# c116-vclfo.net
KiCad netlist of a schematic drawn in EAGLE
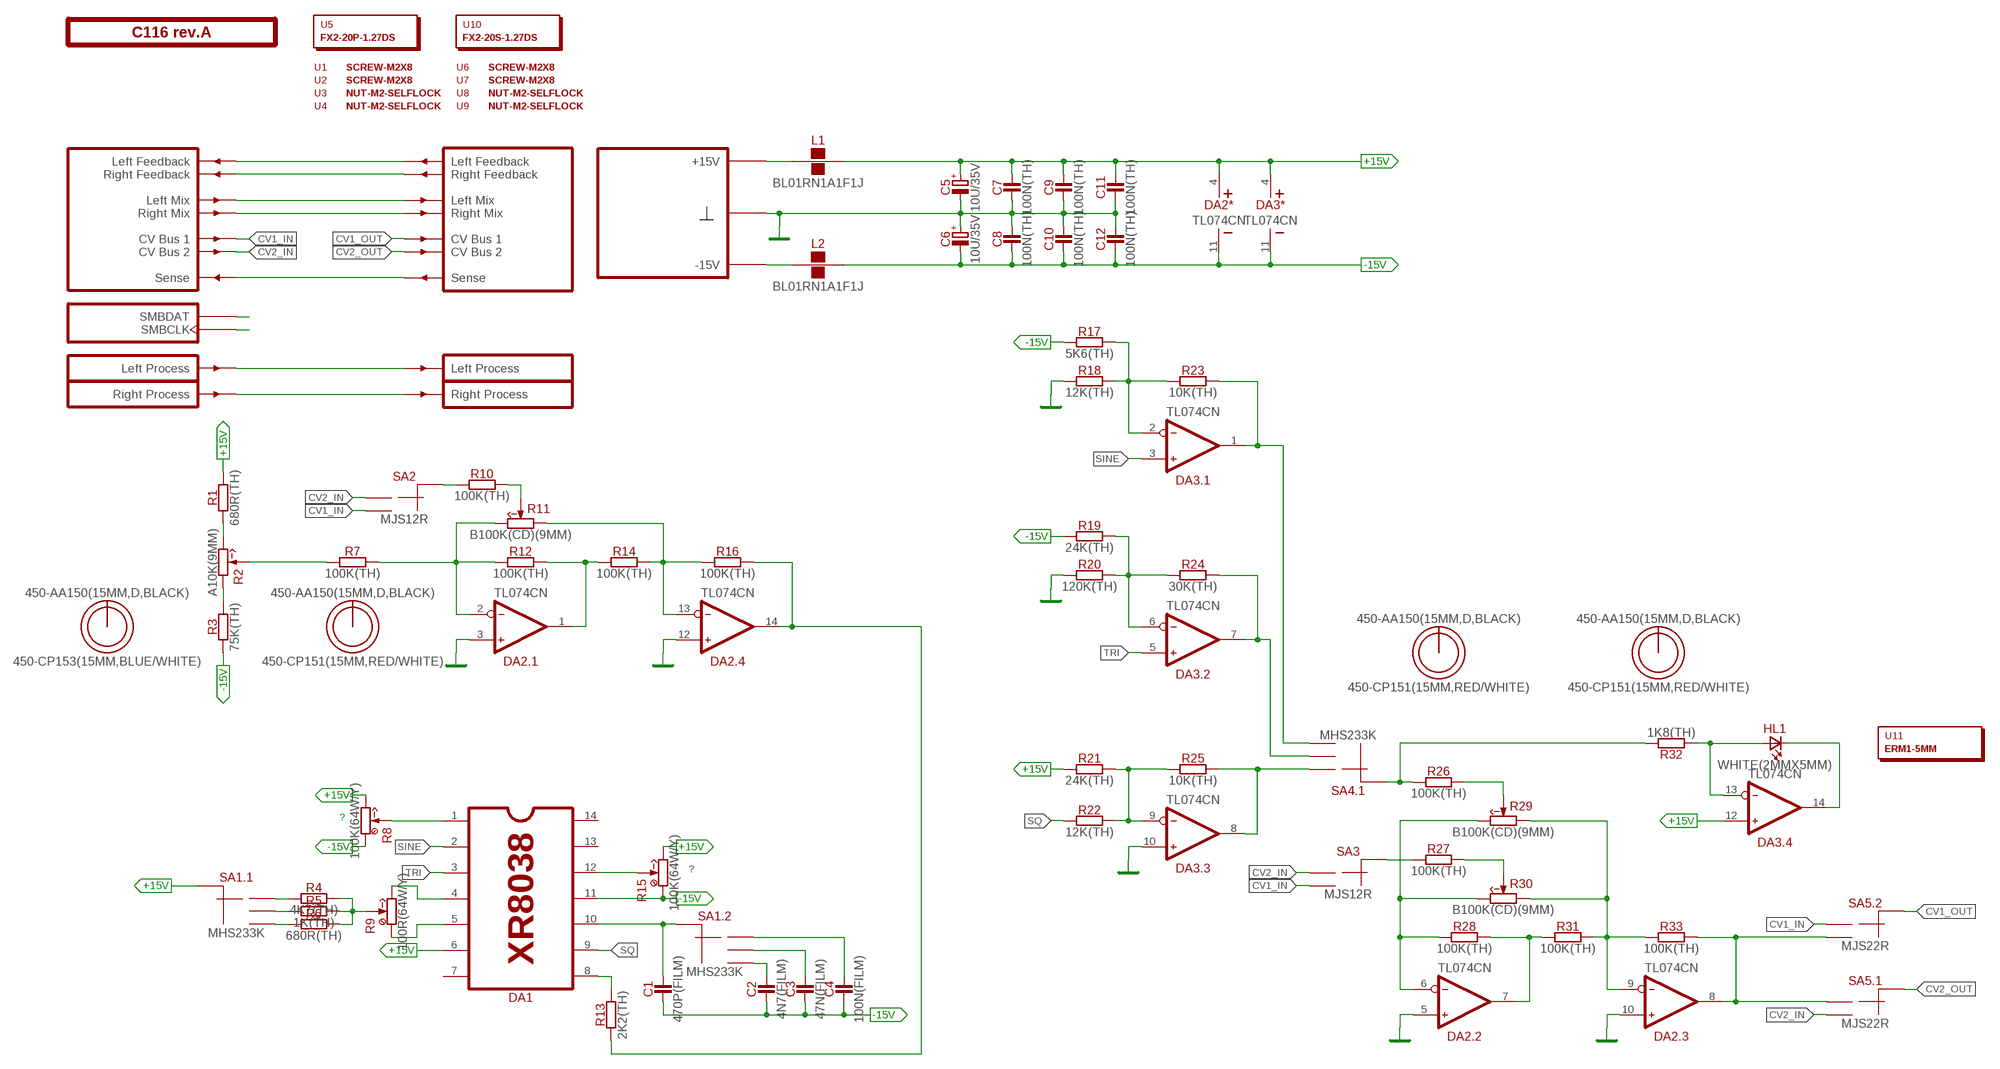
[diagram p0: schematic, sheet 1]

(export (version "E")
  (design (tool "Eeschema 10.0.6"))
  (components
    (comp (ref "C1")
      (value "470P(FILM)")
      (footprint "eagle-import:C050-055X075")
      (libsource (lib "eagle-import") (part "?470P(FILM)"))
    )
    (comp (ref "C2")
      (value "4N7(FILM)")
      (footprint "eagle-import:C050-025X075")
      (libsource (lib "eagle-import") (part "?4N7(FILM)"))
    )
    (comp (ref "C3")
      (value "47N(FILM)")
      (footprint "eagle-import:C050-025X075")
      (libsource (lib "eagle-import") (part "?47N(FILM)"))
    )
    (comp (ref "C4")
      (value "100N(FILM)")
      (footprint "eagle-import:C050-025X075")
      (libsource (lib "eagle-import") (part "?100N(FILM)"))
    )
    (comp (ref "C5")
      (value "10U/35V")
      (footprint "eagle-import:E2-5")
      (libsource (lib "eagle-import") (part "?10U/35V"))
    )
    (comp (ref "C6")
      (value "10U/35V")
      (footprint "eagle-import:E2-5")
      (libsource (lib "eagle-import") (part "?10U/35V"))
    )
    (comp (ref "C7")
      (value "100N(TH)")
      (footprint "eagle-import:C050-024X044")
      (libsource (lib "eagle-import") (part "?100N(TH)"))
    )
    (comp (ref "C8")
      (value "100N(TH)")
      (footprint "eagle-import:C050-024X044")
      (libsource (lib "eagle-import") (part "?100N(TH)"))
    )
    (comp (ref "C9")
      (value "100N(TH)")
      (footprint "eagle-import:C050-024X044")
      (libsource (lib "eagle-import") (part "?100N(TH)"))
    )
    (comp (ref "C10")
      (value "100N(TH)")
      (footprint "eagle-import:C050-024X044")
      (libsource (lib "eagle-import") (part "?100N(TH)"))
    )
    (comp (ref "C11")
      (value "100N(TH)")
      (footprint "eagle-import:C050-024X044")
      (libsource (lib "eagle-import") (part "?100N(TH)"))
    )
    (comp (ref "C12")
      (value "100N(TH)")
      (footprint "eagle-import:C050-024X044")
      (libsource (lib "eagle-import") (part "?100N(TH)"))
    )
    (comp (ref "DA1")
      (value "XR8038")
      (footprint "eagle-import:DIP-14")
      (libsource (lib "eagle-import") (part "XR8038"))
    )
    (comp (ref "DA2")
      (value "TL074CN")
      (footprint "eagle-import:DIP-14")
      (libsource (lib "eagle-import") (part "TL074CN"))
    )
    (comp (ref "DA3")
      (value "TL074CN")
      (footprint "eagle-import:DIP-14")
      (libsource (lib "eagle-import") (part "TL074CN"))
    )
    (comp (ref "HL1")
      (value "WHITE(2MMX5MM)")
      (footprint "eagle-import:LED2X5")
      (libsource (lib "eagle-import") (part "?(2MMX5MM)WHITE"))
    )
    (comp (ref "L1")
      (value "BL01RN1A1F1J")
      (footprint "eagle-import:BL01RN1A")
      (libsource (lib "eagle-import") (part "BL01RN1A?1F1J"))
    )
    (comp (ref "L2")
      (value "BL01RN1A1F1J")
      (footprint "eagle-import:BL01RN1A")
      (libsource (lib "eagle-import") (part "BL01RN1A?1F1J"))
    )
    (comp (ref "O1")
      (value "450-AA150(15MM,D,BLACK)")
      (footprint "eagle-import:EMPTY")
      (libsource (lib "eagle-import") (part "450-AA?150(15MM,D,BLACK)"))
    )
    (comp (ref "O2")
      (value "450-CP153(15MM,BLUE/WHITE)")
      (footprint "eagle-import:EMPTY")
      (libsource (lib "eagle-import") (part "450-C?P153(15MM,BLUE/WHITE)"))
    )
    (comp (ref "O3")
      (value "450-AA150(15MM,D,BLACK)")
      (footprint "eagle-import:EMPTY")
      (libsource (lib "eagle-import") (part "450-AA?150(15MM,D,BLACK)"))
    )
    (comp (ref "O4")
      (value "450-CP151(15MM,RED/WHITE)")
      (footprint "eagle-import:EMPTY")
      (libsource (lib "eagle-import") (part "450-C?P151(15MM,RED/WHITE)"))
    )
    (comp (ref "O5")
      (value "450-AA150(15MM,D,BLACK)")
      (footprint "eagle-import:EMPTY")
      (libsource (lib "eagle-import") (part "450-AA?150(15MM,D,BLACK)"))
    )
    (comp (ref "O6")
      (value "450-CP151(15MM,RED/WHITE)")
      (footprint "eagle-import:EMPTY")
      (libsource (lib "eagle-import") (part "450-C?P151(15MM,RED/WHITE)"))
    )
    (comp (ref "O7")
      (value "450-AA150(15MM,D,BLACK)")
      (footprint "eagle-import:EMPTY")
      (libsource (lib "eagle-import") (part "450-AA?150(15MM,D,BLACK)"))
    )
    (comp (ref "O8")
      (value "450-CP151(15MM,RED/WHITE)")
      (footprint "eagle-import:EMPTY")
      (libsource (lib "eagle-import") (part "450-C?P151(15MM,RED/WHITE)"))
    )
    (comp (ref "PCB1")
      (value "C116 rev.A")
      (footprint "eagle-import:ST2-BOARD-74")
      (libsource (lib "eagle-import") (part "ST2-BOARD-?74"))
    )
    (comp (ref "R1")
      (value "680R(TH)")
      (footprint "eagle-import:R-0207_10")
      (libsource (lib "eagle-import") (part "?680R(TH)"))
    )
    (comp (ref "R2")
      (value "A10K(9MM)")
      (footprint "eagle-import:RV09-SINGLE")
      (libsource (lib "eagle-import") (part "?A10K(9MM)"))
    )
    (comp (ref "R3")
      (value "75K(TH)")
      (footprint "eagle-import:R-0207_10")
      (libsource (lib "eagle-import") (part "?75K(TH)"))
    )
    (comp (ref "R4")
      (value "4K7(TH)")
      (footprint "eagle-import:R-0207_10")
      (libsource (lib "eagle-import") (part "?4K7(TH)"))
    )
    (comp (ref "R5")
      (value "1K(TH)")
      (footprint "eagle-import:R-0207_10")
      (libsource (lib "eagle-import") (part "?1K(TH)"))
    )
    (comp (ref "R6")
      (value "680R(TH)")
      (footprint "eagle-import:R-0207_10")
      (libsource (lib "eagle-import") (part "?680R(TH)"))
    )
    (comp (ref "R7")
      (value "100K(TH)")
      (footprint "eagle-import:R-0207_10")
      (libsource (lib "eagle-import") (part "?100K(TH)"))
    )
    (comp (ref "R8")
      (value "100K(64W/Y)")
      (footprint "eagle-import:64W")
      (libsource (lib "eagle-import") (part "?(64W/Y)100K"))
    )
    (comp (ref "R9")
      (value "100R(64W/Y)")
      (footprint "eagle-import:64W")
      (libsource (lib "eagle-import") (part "?(64W/Y)100R"))
    )
    (comp (ref "R10")
      (value "100K(TH)")
      (footprint "eagle-import:R-0207_10")
      (libsource (lib "eagle-import") (part "?100K(TH)"))
    )
    (comp (ref "R11")
      (value "B100K(CD)(9MM)")
      (footprint "eagle-import:RV09-SINGLE")
      (libsource (lib "eagle-import") (part "?B100K(CD)(9MM)"))
    )
    (comp (ref "R12")
      (value "100K(TH)")
      (footprint "eagle-import:R-0207_10")
      (libsource (lib "eagle-import") (part "?100K(TH)"))
    )
    (comp (ref "R13")
      (value "2K2(TH)")
      (footprint "eagle-import:R-0207_10")
      (libsource (lib "eagle-import") (part "?2K2(TH)"))
    )
    (comp (ref "R14")
      (value "100K(TH)")
      (footprint "eagle-import:R-0207_10")
      (libsource (lib "eagle-import") (part "?100K(TH)"))
    )
    (comp (ref "R15")
      (value "100K(64W/Y)")
      (footprint "eagle-import:64W")
      (libsource (lib "eagle-import") (part "?(64W/Y)100K"))
    )
    (comp (ref "R16")
      (value "100K(TH)")
      (footprint "eagle-import:R-0207_10")
      (libsource (lib "eagle-import") (part "?100K(TH)"))
    )
    (comp (ref "R17")
      (value "5K6(TH)")
      (footprint "eagle-import:R-0207_10")
      (libsource (lib "eagle-import") (part "?5K6(TH)"))
    )
    (comp (ref "R18")
      (value "12K(TH)")
      (footprint "eagle-import:R-0207_10")
      (libsource (lib "eagle-import") (part "?12K(TH)"))
    )
    (comp (ref "R19")
      (value "24K(TH)")
      (footprint "eagle-import:R-0207_10")
      (libsource (lib "eagle-import") (part "?24K(TH)"))
    )
    (comp (ref "R20")
      (value "120K(TH)")
      (footprint "eagle-import:R-0207_10")
      (libsource (lib "eagle-import") (part "?120K(TH)"))
    )
    (comp (ref "R21")
      (value "24K(TH)")
      (footprint "eagle-import:R-0207_10")
      (libsource (lib "eagle-import") (part "?24K(TH)"))
    )
    (comp (ref "R22")
      (value "12K(TH)")
      (footprint "eagle-import:R-0207_10")
      (libsource (lib "eagle-import") (part "?12K(TH)"))
    )
    (comp (ref "R23")
      (value "10K(TH)")
      (footprint "eagle-import:R-0207_10")
      (libsource (lib "eagle-import") (part "?10K(TH)"))
    )
    (comp (ref "R24")
      (value "30K(TH)")
      (footprint "eagle-import:R-0207_10")
      (libsource (lib "eagle-import") (part "?30K(TH)"))
    )
    (comp (ref "R25")
      (value "10K(TH)")
      (footprint "eagle-import:R-0207_10")
      (libsource (lib "eagle-import") (part "?10K(TH)"))
    )
    (comp (ref "R26")
      (value "100K(TH)")
      (footprint "eagle-import:R-0207_10")
      (libsource (lib "eagle-import") (part "?100K(TH)"))
    )
    (comp (ref "R27")
      (value "100K(TH)")
      (footprint "eagle-import:R-0207_10")
      (libsource (lib "eagle-import") (part "?100K(TH)"))
    )
    (comp (ref "R28")
      (value "100K(TH)")
      (footprint "eagle-import:R-0207_10")
      (libsource (lib "eagle-import") (part "?100K(TH)"))
    )
    (comp (ref "R29")
      (value "B100K(CD)(9MM)")
      (footprint "eagle-import:RV09-SINGLE")
      (libsource (lib "eagle-import") (part "?B100K(CD)(9MM)"))
    )
    (comp (ref "R30")
      (value "B100K(CD)(9MM)")
      (footprint "eagle-import:RV09-SINGLE")
      (libsource (lib "eagle-import") (part "?B100K(CD)(9MM)"))
    )
    (comp (ref "R31")
      (value "100K(TH)")
      (footprint "eagle-import:R-0207_10")
      (libsource (lib "eagle-import") (part "?100K(TH)"))
    )
    (comp (ref "R32")
      (value "1K8(TH)")
      (footprint "eagle-import:R-0207_10")
      (libsource (lib "eagle-import") (part "?1K8(TH)"))
    )
    (comp (ref "R33")
      (value "100K(TH)")
      (footprint "eagle-import:R-0207_10")
      (libsource (lib "eagle-import") (part "?100K(TH)"))
    )
    (comp (ref "SA1")
      (value "MHS233K")
      (footprint "eagle-import:APEM-MHS233K")
      (libsource (lib "eagle-import") (part "MHS233K"))
    )
    (comp (ref "SA2")
      (value "MJS12R")
      (footprint "eagle-import:APEM-MJS12R")
      (libsource (lib "eagle-import") (part "MJS12R"))
    )
    (comp (ref "SA3")
      (value "MJS12R")
      (footprint "eagle-import:APEM-MJS12R")
      (libsource (lib "eagle-import") (part "MJS12R"))
    )
    (comp (ref "SA4")
      (value "MHS233K")
      (footprint "eagle-import:APEM-MHS233K")
      (libsource (lib "eagle-import") (part "MHS233K"))
    )
    (comp (ref "SA5")
      (value "MJS22R")
      (footprint "eagle-import:APEM-MJS22R")
      (libsource (lib "eagle-import") (part "MJS22R"))
    )
    (comp (ref "U1")
      (value "SCREW-M2X8")
      (footprint "eagle-import:EMPTY")
      (libsource (lib "eagle-import") (part "?SCREW-M2X8"))
    )
    (comp (ref "U2")
      (value "SCREW-M2X8")
      (footprint "eagle-import:EMPTY")
      (libsource (lib "eagle-import") (part "?SCREW-M2X8"))
    )
    (comp (ref "U3")
      (value "NUT-M2-SELFLOCK")
      (footprint "eagle-import:EMPTY")
      (libsource (lib "eagle-import") (part "?NUT-M2-SELFLOCK"))
    )
    (comp (ref "U4")
      (value "NUT-M2-SELFLOCK")
      (footprint "eagle-import:EMPTY")
      (libsource (lib "eagle-import") (part "?NUT-M2-SELFLOCK"))
    )
    (comp (ref "U5")
      (value "FX2-20P-1.27DS")
      (footprint "eagle-import:EMPTY")
      (libsource (lib "eagle-import") (part "?FX2-20P-1.27DS"))
    )
    (comp (ref "U6")
      (value "SCREW-M2X8")
      (footprint "eagle-import:EMPTY")
      (libsource (lib "eagle-import") (part "?SCREW-M2X8"))
    )
    (comp (ref "U7")
      (value "SCREW-M2X8")
      (footprint "eagle-import:EMPTY")
      (libsource (lib "eagle-import") (part "?SCREW-M2X8"))
    )
    (comp (ref "U8")
      (value "NUT-M2-SELFLOCK")
      (footprint "eagle-import:EMPTY")
      (libsource (lib "eagle-import") (part "?NUT-M2-SELFLOCK"))
    )
    (comp (ref "U9")
      (value "NUT-M2-SELFLOCK")
      (footprint "eagle-import:EMPTY")
      (libsource (lib "eagle-import") (part "?NUT-M2-SELFLOCK"))
    )
    (comp (ref "U10")
      (value "FX2-20S-1.27DS")
      (footprint "eagle-import:EMPTY")
      (libsource (lib "eagle-import") (part "?FX2-20S-1.27DS"))
    )
    (comp (ref "U11")
      (value "ERM1-5MM")
      (footprint "eagle-import:EMPTY")
      (libsource (lib "eagle-import") (part "?ERM1-5MM"))
    )
  )
  (nets
    (net (code "1") (name "+15V") (class "Default")
      (node (ref "C11") (pin "2") (pinfunction "2_2") (pintype "passive"))
      (node (ref "C5") (pin "+") (pinfunction "+_+") (pintype "passive"))
      (node (ref "C7") (pin "2") (pinfunction "2_2") (pintype "passive"))
      (node (ref "C9") (pin "2") (pinfunction "2_2") (pintype "passive"))
      (node (ref "DA1") (pin "6") (pinfunction "6_6") (pintype "bidirectional"))
      (node (ref "DA2") (pin "4") (pinfunction "V+_4") (pintype "power_in"))
      (node (ref "DA3") (pin "12") (pinfunction "IN+_12") (pintype "input"))
      (node (ref "DA3") (pin "4") (pinfunction "V+_4") (pintype "power_in"))
      (node (ref "L1") (pin "2") (pinfunction "2_2") (pintype "passive"))
      (node (ref "R1") (pin "2") (pinfunction "2_2") (pintype "passive"))
      (node (ref "R15") (pin "3") (pinfunction "CW_3") (pintype "passive"))
      (node (ref "R21") (pin "1") (pinfunction "1_1") (pintype "passive"))
      (node (ref "R8") (pin "3") (pinfunction "CW_3") (pintype "passive"))
      (node (ref "SA1") (pin "CMN") (pinfunction "CM_CMN") (pintype "passive"))
    )
    (net (code "2") (name "-15V") (class "Default")
      (node (ref "C1") (pin "1") (pinfunction "1_1") (pintype "passive"))
      (node (ref "C10") (pin "1") (pinfunction "1_1") (pintype "passive"))
      (node (ref "C12") (pin "1") (pinfunction "1_1") (pintype "passive"))
      (node (ref "C2") (pin "1") (pinfunction "1_1") (pintype "passive"))
      (node (ref "C3") (pin "1") (pinfunction "1_1") (pintype "passive"))
      (node (ref "C4") (pin "1") (pinfunction "1_1") (pintype "passive"))
      (node (ref "C6") (pin "-") (pinfunction "-_-") (pintype "passive"))
      (node (ref "C8") (pin "1") (pinfunction "1_1") (pintype "passive"))
      (node (ref "DA1") (pin "11") (pinfunction "11_11") (pintype "bidirectional"))
      (node (ref "DA2") (pin "11") (pinfunction "V-_11") (pintype "power_in"))
      (node (ref "DA3") (pin "11") (pinfunction "V-_11") (pintype "power_in"))
      (node (ref "L2") (pin "2") (pinfunction "2_2") (pintype "passive"))
      (node (ref "R15") (pin "1") (pinfunction "CCW_1") (pintype "passive"))
      (node (ref "R17") (pin "1") (pinfunction "1_1") (pintype "passive"))
      (node (ref "R19") (pin "1") (pinfunction "1_1") (pintype "passive"))
      (node (ref "R3") (pin "1") (pinfunction "1_1") (pintype "passive"))
      (node (ref "R8") (pin "1") (pinfunction "CCW_1") (pintype "passive"))
    )
    (net (code "3") (name "CV1_IN") (class "Default")
      (node (ref "PCB1") (pin "ACV1") (pinfunction "CV1_ACV1") (pintype "bidirectional"))
      (node (ref "SA2") (pin "NO") (pinfunction "2_NO") (pintype "passive"))
      (node (ref "SA3") (pin "NO") (pinfunction "2_NO") (pintype "passive"))
      (node (ref "SA5") (pin "NC2") (pinfunction "1_NC2") (pintype "passive"))
    )
    (net (code "4") (name "CV1_OUT") (class "Default")
      (node (ref "PCB1") (pin "ACV1'") (pinfunction "CV1'_ACV1'") (pintype "bidirectional"))
      (node (ref "SA5") (pin "C2") (pinfunction "CM_C2") (pintype "passive"))
    )
    (net (code "5") (name "CV2_IN") (class "Default")
      (node (ref "PCB1") (pin "ACV2") (pinfunction "CV2_ACV2") (pintype "bidirectional"))
      (node (ref "SA2") (pin "NC") (pinfunction "1_NC") (pintype "passive"))
      (node (ref "SA3") (pin "NC") (pinfunction "1_NC") (pintype "passive"))
      (node (ref "SA5") (pin "NO1") (pinfunction "2_NO1") (pintype "passive"))
    )
    (net (code "6") (name "CV2_OUT") (class "Default")
      (node (ref "PCB1") (pin "ACV2'") (pinfunction "CV2'_ACV2'") (pintype "bidirectional"))
      (node (ref "SA5") (pin "C1") (pinfunction "CM_C1") (pintype "passive"))
    )
    (net (code "7") (name "GND") (class "Default")
      (node (ref "C10") (pin "2") (pinfunction "2_2") (pintype "passive"))
      (node (ref "C11") (pin "1") (pinfunction "1_1") (pintype "passive"))
      (node (ref "C12") (pin "2") (pinfunction "2_2") (pintype "passive"))
      (node (ref "C5") (pin "-") (pinfunction "-_-") (pintype "passive"))
      (node (ref "C6") (pin "+") (pinfunction "+_+") (pintype "passive"))
      (node (ref "C7") (pin "1") (pinfunction "1_1") (pintype "passive"))
      (node (ref "C8") (pin "2") (pinfunction "2_2") (pintype "passive"))
      (node (ref "C9") (pin "1") (pinfunction "1_1") (pintype "passive"))
      (node (ref "DA2") (pin "10") (pinfunction "IN+_10") (pintype "input"))
      (node (ref "DA2") (pin "12") (pinfunction "IN+_12") (pintype "input"))
      (node (ref "DA2") (pin "3") (pinfunction "IN+_3") (pintype "input"))
      (node (ref "DA2") (pin "5") (pinfunction "IN+_5") (pintype "input"))
      (node (ref "DA3") (pin "10") (pinfunction "IN+_10") (pintype "input"))
      (node (ref "PCB1") (pin "B4") (pinfunction "GND_B4") (pintype "bidirectional"))
      (node (ref "PCB1") (pin "B4'") (pinfunction "GND_B4'") (pintype "bidirectional"))
      (node (ref "PCB1") (pin "B5") (pinfunction "GND_B5") (pintype "bidirectional"))
      (node (ref "PCB1") (pin "B5'") (pinfunction "GND_B5'") (pintype "bidirectional"))
      (node (ref "PCB1") (pin "B6") (pinfunction "GND_B6") (pintype "bidirectional"))
      (node (ref "PCB1") (pin "B6'") (pinfunction "GND_B6'") (pintype "bidirectional"))
      (node (ref "PCB1") (pin "B7") (pinfunction "GND_B7") (pintype "bidirectional"))
      (node (ref "PCB1") (pin "B7'") (pinfunction "GND_B7'") (pintype "bidirectional"))
      (node (ref "PCB1") (pin "B8") (pinfunction "GND_B8") (pintype "bidirectional"))
      (node (ref "PCB1") (pin "B8'") (pinfunction "GND_B8'") (pintype "bidirectional"))
      (node (ref "R18") (pin "1") (pinfunction "1_1") (pintype "passive"))
      (node (ref "R20") (pin "1") (pinfunction "1_1") (pintype "passive"))
    )
    (net (code "8") (name "Net-(DA1-Pad1)") (class "Default")
      (node (ref "DA1") (pin "1") (pinfunction "1_1") (pintype "bidirectional"))
      (node (ref "R8") (pin "S") (pinfunction "W_S") (pintype "passive"))
      (node (ref "R8") (pin "S@1") (pinfunction "W_S@1") (pintype "passive"))
    )
    (net (code "9") (name "Net-(DA1-Pad8)") (class "Default")
      (node (ref "DA1") (pin "8") (pinfunction "8_8") (pintype "bidirectional"))
      (node (ref "R13") (pin "2") (pinfunction "2_2") (pintype "passive"))
    )
    (net (code "10") (name "Net-(DA1-Pad12)") (class "Default")
      (node (ref "DA1") (pin "12") (pinfunction "12_12") (pintype "bidirectional"))
      (node (ref "R15") (pin "S") (pinfunction "W_S") (pintype "passive"))
      (node (ref "R15") (pin "S@1") (pinfunction "W_S@1") (pintype "passive"))
    )
    (net (code "11") (name "Net-(DA2B-IN-)") (class "Default")
      (node (ref "DA2") (pin "2") (pinfunction "IN-_2") (pintype "input"))
      (node (ref "R11") (pin "3") (pinfunction "CW_3") (pintype "passive"))
      (node (ref "R12") (pin "1") (pinfunction "1_1") (pintype "passive"))
      (node (ref "R7") (pin "2") (pinfunction "2_2") (pintype "passive"))
    )
    (net (code "12") (name "Net-(DA2B-OUT)") (class "Default")
      (node (ref "DA2") (pin "1") (pinfunction "OUT_1") (pintype "output"))
      (node (ref "R12") (pin "2") (pinfunction "2_2") (pintype "passive"))
      (node (ref "R14") (pin "1") (pinfunction "1_1") (pintype "passive"))
    )
    (net (code "13") (name "Net-(DA2C-IN-)") (class "Default")
      (node (ref "DA2") (pin "6") (pinfunction "IN-_6") (pintype "input"))
      (node (ref "R28") (pin "1") (pinfunction "1_1") (pintype "passive"))
      (node (ref "R29") (pin "3") (pinfunction "CW_3") (pintype "passive"))
      (node (ref "R30") (pin "3") (pinfunction "CW_3") (pintype "passive"))
    )
    (net (code "14") (name "Net-(DA2C-OUT)") (class "Default")
      (node (ref "DA2") (pin "7") (pinfunction "OUT_7") (pintype "output"))
      (node (ref "R28") (pin "2") (pinfunction "2_2") (pintype "passive"))
      (node (ref "R31") (pin "1") (pinfunction "1_1") (pintype "passive"))
    )
    (net (code "15") (name "Net-(DA2D-IN-)") (class "Default")
      (node (ref "DA2") (pin "9") (pinfunction "IN-_9") (pintype "input"))
      (node (ref "R29") (pin "1") (pinfunction "CCW_1") (pintype "passive"))
      (node (ref "R30") (pin "1") (pinfunction "CCW_1") (pintype "passive"))
      (node (ref "R31") (pin "2") (pinfunction "2_2") (pintype "passive"))
      (node (ref "R33") (pin "1") (pinfunction "1_1") (pintype "passive"))
    )
    (net (code "16") (name "Net-(DA2D-OUT)") (class "Default")
      (node (ref "DA2") (pin "8") (pinfunction "OUT_8") (pintype "output"))
      (node (ref "R33") (pin "2") (pinfunction "2_2") (pintype "passive"))
      (node (ref "SA5") (pin "NC1") (pinfunction "1_NC1") (pintype "passive"))
      (node (ref "SA5") (pin "NO2") (pinfunction "2_NO2") (pintype "passive"))
    )
    (net (code "17") (name "Net-(DA2E-IN-)") (class "Default")
      (node (ref "DA2") (pin "13") (pinfunction "IN-_13") (pintype "input"))
      (node (ref "R11") (pin "1") (pinfunction "CCW_1") (pintype "passive"))
      (node (ref "R14") (pin "2") (pinfunction "2_2") (pintype "passive"))
      (node (ref "R16") (pin "1") (pinfunction "1_1") (pintype "passive"))
    )
    (net (code "18") (name "Net-(DA2E-OUT)") (class "Default")
      (node (ref "DA2") (pin "14") (pinfunction "OUT_14") (pintype "output"))
      (node (ref "R13") (pin "1") (pinfunction "1_1") (pintype "passive"))
      (node (ref "R16") (pin "2") (pinfunction "2_2") (pintype "passive"))
    )
    (net (code "19") (name "Net-(DA3B-IN-)") (class "Default")
      (node (ref "DA3") (pin "2") (pinfunction "IN-_2") (pintype "input"))
      (node (ref "R17") (pin "2") (pinfunction "2_2") (pintype "passive"))
      (node (ref "R18") (pin "2") (pinfunction "2_2") (pintype "passive"))
      (node (ref "R23") (pin "1") (pinfunction "1_1") (pintype "passive"))
    )
    (net (code "20") (name "Net-(DA3B-OUT)") (class "Default")
      (node (ref "DA3") (pin "1") (pinfunction "OUT_1") (pintype "output"))
      (node (ref "R23") (pin "2") (pinfunction "2_2") (pintype "passive"))
      (node (ref "SA4") (pin "3") (pinfunction "3_3") (pintype "passive"))
    )
    (net (code "21") (name "Net-(DA3C-IN-)") (class "Default")
      (node (ref "DA3") (pin "6") (pinfunction "IN-_6") (pintype "input"))
      (node (ref "R19") (pin "2") (pinfunction "2_2") (pintype "passive"))
      (node (ref "R20") (pin "2") (pinfunction "2_2") (pintype "passive"))
      (node (ref "R24") (pin "1") (pinfunction "1_1") (pintype "passive"))
    )
    (net (code "22") (name "Net-(DA3C-OUT)") (class "Default")
      (node (ref "DA3") (pin "7") (pinfunction "OUT_7") (pintype "output"))
      (node (ref "R24") (pin "2") (pinfunction "2_2") (pintype "passive"))
      (node (ref "SA4") (pin "2") (pinfunction "2_2") (pintype "passive"))
    )
    (net (code "23") (name "Net-(DA3D-IN-)") (class "Default")
      (node (ref "DA3") (pin "9") (pinfunction "IN-_9") (pintype "input"))
      (node (ref "R21") (pin "2") (pinfunction "2_2") (pintype "passive"))
      (node (ref "R22") (pin "2") (pinfunction "2_2") (pintype "passive"))
      (node (ref "R25") (pin "1") (pinfunction "1_1") (pintype "passive"))
    )
    (net (code "24") (name "Net-(DA3D-OUT)") (class "Default")
      (node (ref "DA3") (pin "8") (pinfunction "OUT_8") (pintype "output"))
      (node (ref "R25") (pin "2") (pinfunction "2_2") (pintype "passive"))
      (node (ref "SA4") (pin "1") (pinfunction "1_1") (pintype "passive"))
    )
    (net (code "25") (name "Net-(DA3E-IN-)") (class "Default")
      (node (ref "DA3") (pin "13") (pinfunction "IN-_13") (pintype "input"))
      (node (ref "HL1") (pin "A") (pinfunction "A_A") (pintype "passive"))
      (node (ref "R32") (pin "1") (pinfunction "1_1") (pintype "passive"))
    )
    (net (code "26") (name "Net-(DA3E-OUT)") (class "Default")
      (node (ref "DA3") (pin "14") (pinfunction "OUT_14") (pintype "output"))
      (node (ref "HL1") (pin "K") (pinfunction "C_K") (pintype "passive"))
    )
    (net (code "27") (name "Net-(L1-Pad1)") (class "Default")
      (node (ref "L1") (pin "1") (pinfunction "1_1") (pintype "passive"))
      (node (ref "PCB1") (pin "A+15") (pinfunction "P+15V_A+15") (pintype "bidirectional"))
      (node (ref "PCB1") (pin "A+15'") (pinfunction "P+15V_A+15'") (pintype "bidirectional"))
      (node (ref "PCB1") (pin "B+15") (pinfunction "P+15V_B+15") (pintype "bidirectional"))
      (node (ref "PCB1") (pin "B+15'") (pinfunction "P+15V_B+15'") (pintype "bidirectional"))
    )
    (net (code "28") (name "Net-(L2-Pad1)") (class "Default")
      (node (ref "L2") (pin "1") (pinfunction "1_1") (pintype "passive"))
      (node (ref "PCB1") (pin "A-15") (pinfunction "P-15V_A-15") (pintype "bidirectional"))
      (node (ref "PCB1") (pin "A-15'") (pinfunction "P-15V_A-15'") (pintype "bidirectional"))
      (node (ref "PCB1") (pin "B-15") (pinfunction "P-15V_B-15") (pintype "bidirectional"))
      (node (ref "PCB1") (pin "B-15'") (pinfunction "P-15V_B-15'") (pintype "bidirectional"))
    )
    (net (code "29") (name "Net-(PCB1B-INL)") (class "Default")
      (node (ref "PCB1") (pin "BINL") (pinfunction "INL_BINL") (pintype "bidirectional"))
      (node (ref "PCB1") (pin "BOUTL'") (pinfunction "OUTL_BOUTL'") (pintype "bidirectional"))
    )
    (net (code "30") (name "Net-(PCB1C-INR)") (class "Default")
      (node (ref "PCB1") (pin "BINR") (pinfunction "INR_BINR") (pintype "bidirectional"))
      (node (ref "PCB1") (pin "BOUTR'") (pinfunction "OUTR_BOUTR'") (pintype "bidirectional"))
    )
    (net (code "31") (name "Net-(PCB1F-LFBK)") (class "Default")
      (node (ref "PCB1") (pin "ALFBK") (pinfunction "LFBK_ALFBK") (pintype "bidirectional"))
      (node (ref "PCB1") (pin "ALFBK'") (pinfunction "LFBK'_ALFBK'") (pintype "bidirectional"))
    )
    (net (code "32") (name "Net-(PCB1F-LMIX)") (class "Default")
      (node (ref "PCB1") (pin "ALMIX") (pinfunction "LMIX_ALMIX") (pintype "bidirectional"))
      (node (ref "PCB1") (pin "ALMIX'") (pinfunction "LMIX'_ALMIX'") (pintype "bidirectional"))
    )
    (net (code "33") (name "Net-(PCB1F-RFBK)") (class "Default")
      (node (ref "PCB1") (pin "ARFBK") (pinfunction "RFBK_ARFBK") (pintype "bidirectional"))
      (node (ref "PCB1") (pin "ARFBK'") (pinfunction "RFBK'_ARFBK'") (pintype "bidirectional"))
    )
    (net (code "34") (name "Net-(PCB1F-RMIX)") (class "Default")
      (node (ref "PCB1") (pin "ARMIX") (pinfunction "RMIX_ARMIX") (pintype "bidirectional"))
      (node (ref "PCB1") (pin "ARMIX'") (pinfunction "RMIX'_ARMIX'") (pintype "bidirectional"))
    )
    (net (code "35") (name "Net-(PCB1F-SENSE)") (class "Default")
      (node (ref "PCB1") (pin "BSENSE") (pinfunction "SENSE_BSENSE") (pintype "bidirectional"))
      (node (ref "PCB1") (pin "BSENSE'") (pinfunction "SENSE'_BSENSE'") (pintype "bidirectional"))
    )
    (net (code "36") (name "Net-(PCB1H-SMBCLK-PadASMBCLK')") (class "Default")
      (node (ref "PCB1") (pin "ASMBCLK") (pinfunction "SMBCLK_ASMBCLK") (pintype "bidirectional"))
      (node (ref "PCB1") (pin "ASMBCLK'") (pinfunction "SMBCLK_ASMBCLK'") (pintype "bidirectional"))
    )
    (net (code "37") (name "Net-(PCB1H-SMBDAT-PadASMBDAT')") (class "Default")
      (node (ref "PCB1") (pin "ASMBDAT") (pinfunction "SMBDAT_ASMBDAT") (pintype "bidirectional"))
      (node (ref "PCB1") (pin "ASMBDAT'") (pinfunction "SMBDAT_ASMBDAT'") (pintype "bidirectional"))
    )
    (net (code "38") (name "Net-(R2-CCW)") (class "Default")
      (node (ref "R2") (pin "1") (pinfunction "CCW_1") (pintype "passive"))
      (node (ref "R3") (pin "2") (pinfunction "2_2") (pintype "passive"))
    )
    (net (code "39") (name "Net-(R2-CW)") (class "Default")
      (node (ref "R1") (pin "1") (pinfunction "1_1") (pintype "passive"))
      (node (ref "R2") (pin "3") (pinfunction "CW_3") (pintype "passive"))
    )
    (net (code "40") (name "Net-(R2-W)") (class "Default")
      (node (ref "R2") (pin "2") (pinfunction "W_2") (pintype "passive"))
      (node (ref "R7") (pin "1") (pinfunction "1_1") (pintype "passive"))
    )
    (net (code "41") (name "Net-(R4-Pad1)") (class "Default")
      (node (ref "R4") (pin "1") (pinfunction "1_1") (pintype "passive"))
      (node (ref "SA1") (pin "1") (pinfunction "1_1") (pintype "passive"))
    )
    (net (code "42") (name "Net-(R4-Pad2)") (class "Default")
      (node (ref "R4") (pin "2") (pinfunction "2_2") (pintype "passive"))
      (node (ref "R5") (pin "2") (pinfunction "2_2") (pintype "passive"))
      (node (ref "R6") (pin "2") (pinfunction "2_2") (pintype "passive"))
      (node (ref "R9") (pin "S") (pinfunction "W_S") (pintype "passive"))
      (node (ref "R9") (pin "S@1") (pinfunction "W_S@1") (pintype "passive"))
    )
    (net (code "43") (name "Net-(R5-Pad1)") (class "Default")
      (node (ref "R5") (pin "1") (pinfunction "1_1") (pintype "passive"))
      (node (ref "SA1") (pin "2") (pinfunction "2_2") (pintype "passive"))
    )
    (net (code "44") (name "Net-(R6-Pad1)") (class "Default")
      (node (ref "R6") (pin "1") (pinfunction "1_1") (pintype "passive"))
      (node (ref "SA1") (pin "3") (pinfunction "3_3") (pintype "passive"))
    )
    (net (code "45") (name "Net-(R9-CCW)") (class "Default")
      (node (ref "DA1") (pin "5") (pinfunction "5_5") (pintype "bidirectional"))
      (node (ref "R9") (pin "1") (pinfunction "CCW_1") (pintype "passive"))
    )
    (net (code "46") (name "Net-(R9-CW)") (class "Default")
      (node (ref "DA1") (pin "4") (pinfunction "4_4") (pintype "bidirectional"))
      (node (ref "R9") (pin "3") (pinfunction "CW_3") (pintype "passive"))
    )
    (net (code "47") (name "Net-(R11-W)") (class "Default")
      (node (ref "R10") (pin "2") (pinfunction "2_2") (pintype "passive"))
      (node (ref "R11") (pin "2") (pinfunction "W_2") (pintype "passive"))
    )
    (net (code "48") (name "Net-(R29-W)") (class "Default")
      (node (ref "R26") (pin "2") (pinfunction "2_2") (pintype "passive"))
      (node (ref "R29") (pin "2") (pinfunction "W_2") (pintype "passive"))
    )
    (net (code "49") (name "Net-(R30-W)") (class "Default")
      (node (ref "R27") (pin "2") (pinfunction "2_2") (pintype "passive"))
      (node (ref "R30") (pin "2") (pinfunction "W_2") (pintype "passive"))
    )
    (net (code "50") (name "Net-(SA1B-1)") (class "Default")
      (node (ref "C4") (pin "2") (pinfunction "2_2") (pintype "passive"))
      (node (ref "SA1") (pin "1'") (pinfunction "1_1'") (pintype "passive"))
    )
    (net (code "51") (name "Net-(SA1B-2)") (class "Default")
      (node (ref "C3") (pin "2") (pinfunction "2_2") (pintype "passive"))
      (node (ref "SA1") (pin "2'") (pinfunction "2_2'") (pintype "passive"))
    )
    (net (code "52") (name "Net-(SA1B-3)") (class "Default")
      (node (ref "C2") (pin "2") (pinfunction "2_2") (pintype "passive"))
      (node (ref "SA1") (pin "3'") (pinfunction "3_3'") (pintype "passive"))
    )
    (net (code "53") (name "Net-(SA1B-CM)") (class "Default")
      (node (ref "C1") (pin "2") (pinfunction "2_2") (pintype "passive"))
      (node (ref "DA1") (pin "10") (pinfunction "10_10") (pintype "bidirectional"))
      (node (ref "SA1") (pin "CMN'") (pinfunction "CM_CMN'") (pintype "passive"))
    )
    (net (code "54") (name "Net-(SA2-CM)") (class "Default")
      (node (ref "R10") (pin "1") (pinfunction "1_1") (pintype "passive"))
      (node (ref "SA2") (pin "C") (pinfunction "CM_C") (pintype "passive"))
    )
    (net (code "55") (name "Net-(SA3-CM)") (class "Default")
      (node (ref "R27") (pin "1") (pinfunction "1_1") (pintype "passive"))
      (node (ref "SA3") (pin "C") (pinfunction "CM_C") (pintype "passive"))
    )
    (net (code "56") (name "Net-(SA4A-CM)") (class "Default")
      (node (ref "R26") (pin "1") (pinfunction "1_1") (pintype "passive"))
      (node (ref "R32") (pin "2") (pinfunction "2_2") (pintype "passive"))
      (node (ref "SA4") (pin "CMN") (pinfunction "CM_CMN") (pintype "passive"))
    )
    (net (code "57") (name "SINE") (class "Default")
      (node (ref "DA1") (pin "2") (pinfunction "2_2") (pintype "bidirectional"))
      (node (ref "DA3") (pin "3") (pinfunction "IN+_3") (pintype "input"))
    )
    (net (code "58") (name "SQ") (class "Default")
      (node (ref "DA1") (pin "9") (pinfunction "9_9") (pintype "bidirectional"))
      (node (ref "R22") (pin "1") (pinfunction "1_1") (pintype "passive"))
    )
    (net (code "59") (name "TRI") (class "Default")
      (node (ref "DA1") (pin "3") (pinfunction "3_3") (pintype "bidirectional"))
      (node (ref "DA3") (pin "5") (pinfunction "IN+_5") (pintype "input"))
    )
    (net (code "60") (name "unconnected-(DA1-Pad7)") (class "Default")
      (node (ref "DA1") (pin "7") (pinfunction "7_7") (pintype "bidirectional"))
    )
    (net (code "61") (name "unconnected-(DA1-Pad13)") (class "Default")
      (node (ref "DA1") (pin "13") (pinfunction "13_13") (pintype "bidirectional"))
    )
    (net (code "62") (name "unconnected-(DA1-Pad14)") (class "Default")
      (node (ref "DA1") (pin "14") (pinfunction "14_14") (pintype "bidirectional"))
    )
  )
)
